# Anti_thept2ENGINE_-V2_2.net
KiCad netlist of a schematic drawn in EAGLE
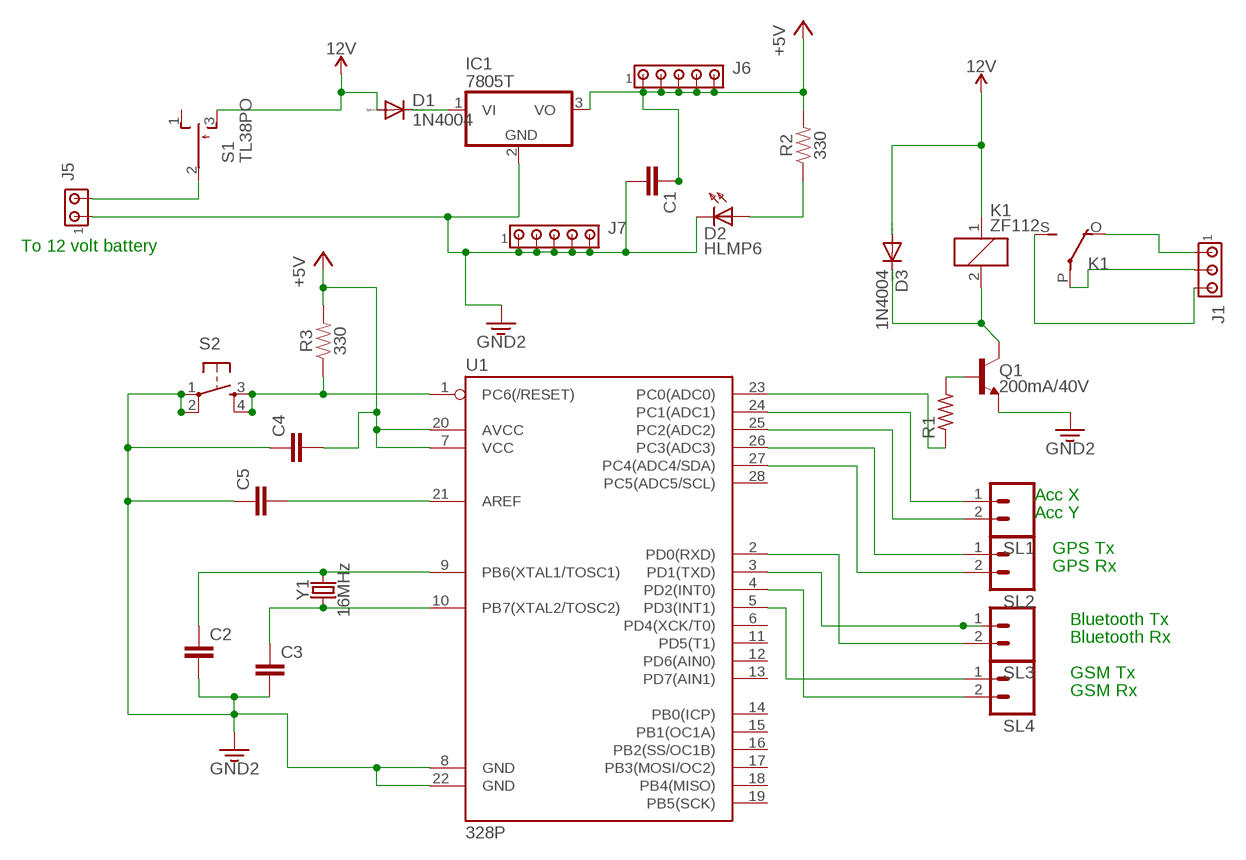
[diagram p0: schematic, sheet 1]

(export (version "E")
  (design (tool "Eeschema 10.0.6"))
  (components
    (comp (ref "C1")
      (value "C5/2.5")
      (footprint "eagle-import:C5B2.5")
      (libsource (lib "eagle-import") (part "C5/2.5"))
    )
    (comp (ref "C2")
      (value "C5/2.5")
      (footprint "eagle-import:C5B2.5")
      (libsource (lib "eagle-import") (part "C5/2.5"))
    )
    (comp (ref "C3")
      (value "C5/2.5")
      (footprint "eagle-import:C5B2.5")
      (libsource (lib "eagle-import") (part "C5/2.5"))
    )
    (comp (ref "C4")
      (value "C5/2.5")
      (footprint "eagle-import:C5B2.5")
      (libsource (lib "eagle-import") (part "C5/2.5"))
    )
    (comp (ref "C5")
      (value "C5/2.5")
      (footprint "eagle-import:C5B2.5")
      (libsource (lib "eagle-import") (part "C5/2.5"))
    )
    (comp (ref "D1")
      (value "1N4004")
      (footprint "eagle-import:DO41-10")
      (libsource (lib "eagle-import") (part "1N4004"))
    )
    (comp (ref "D2")
      (value "HLMP6")
      (footprint "eagle-import:HLMP6")
      (fields (field (name "MF") "AGILENT TECHNOLOGIES") (field (name "MPN") "HLMP-6500"))
      (libsource (lib "eagle-import") (part "HLMP6"))
    )
    (comp (ref "D3")
      (value "1N4004")
      (footprint "eagle-import:DO41-10")
      (libsource (lib "eagle-import") (part "1N4004"))
    )
    (comp (ref "IC1")
      (value "7805T")
      (footprint "eagle-import:TO220H")
      (libsource (lib "eagle-import") (part "78T05"))
    )
    (comp (ref "J1")
      (value "MTA03-156")
      (footprint "eagle-import:1X3MTA")
      (libsource (lib "eagle-import") (part "MTA03-156"))
    )
    (comp (ref "J5")
      (value "MTA02-156")
      (footprint "eagle-import:1X2MTA")
      (libsource (lib "eagle-import") (part "MTA02-156"))
    )
    (comp (ref "J6")
      (value "MTA05-100")
      (footprint "eagle-import:10X05MTA")
      (libsource (lib "eagle-import") (part "MTA05-100"))
    )
    (comp (ref "J7")
      (value "MTA05-100")
      (footprint "eagle-import:10X05MTA")
      (libsource (lib "eagle-import") (part "MTA05-100"))
    )
    (comp (ref "K1")
      (value "ZF112")
      (footprint "eagle-import:ZF112")
      (libsource (lib "eagle-import") (part "ZF112"))
    )
    (comp (ref "Q1")
      (value "200mA/40V")
      (footprint "eagle-import:TO-92")
      (libsource (lib "eagle-import") (part "TRANS_NPN-2N3904"))
    )
    (comp (ref "R1")
      (value "R-US_0204/7")
      (footprint "eagle-import:0204_7")
      (libsource (lib "eagle-import") (part "R-US_0204/7"))
    )
    (comp (ref "R2")
      (value "330")
      (footprint "eagle-import:AXIAL-0.3")
      (libsource (lib "eagle-import") (part "330OHM-HORIZ-1/10W-5%"))
    )
    (comp (ref "R3")
      (value "330")
      (footprint "eagle-import:AXIAL-0.3")
      (libsource (lib "eagle-import") (part "330OHM-HORIZ-1/10W-5%"))
    )
    (comp (ref "S1")
      (value "TL38PO")
      (footprint "eagle-import:TL3XPO")
      (libsource (lib "eagle-import") (part "TL38PO"))
    )
    (comp (ref "S2")
      (value "TAC_SWITCHPTH")
      (footprint "eagle-import:TACTILE-PTH")
      (libsource (lib "eagle-import") (part "TAC_SWITCHPTH"))
    )
    (comp (ref "SL1")
      (value "MA02")
      (footprint "eagle-import:02PA")
      (libsource (lib "eagle-import") (part "MA02"))
    )
    (comp (ref "SL2")
      (value "MA02")
      (footprint "eagle-import:02PA")
      (libsource (lib "eagle-import") (part "MA02"))
    )
    (comp (ref "SL3")
      (value "MA02")
      (footprint "eagle-import:02PA")
      (libsource (lib "eagle-import") (part "MA02"))
    )
    (comp (ref "SL4")
      (value "MA02")
      (footprint "eagle-import:02PA")
      (libsource (lib "eagle-import") (part "MA02"))
    )
    (comp (ref "U1")
      (value "328P")
      (footprint "eagle-import:DIP28")
      (libsource (lib "eagle-import") (part "ATMEGA328P_PDIP"))
    )
    (comp (ref "Y1")
      (value "16MHz")
      (footprint "eagle-import:HC49US")
      (libsource (lib "eagle-import") (part "CRYSTAL-16MHZPTH-HC49US"))
    )
  )
  (nets
    (net (code "1") (name "+5V") (class "Default")
      (node (ref "C1") (pin "1") (pinfunction "1_1") (pintype "passive"))
      (node (ref "C4") (pin "2") (pinfunction "2_2") (pintype "passive"))
      (node (ref "IC1") (pin "3") (pinfunction "VO_3") (pintype "passive"))
      (node (ref "J6") (pin "1") (pinfunction "1_1") (pintype "passive"))
      (node (ref "J6") (pin "2") (pinfunction "2_2") (pintype "passive"))
      (node (ref "J6") (pin "3") (pinfunction "3_3") (pintype "passive"))
      (node (ref "J6") (pin "4") (pinfunction "4_4") (pintype "passive"))
      (node (ref "J6") (pin "5") (pinfunction "5_5") (pintype "passive"))
      (node (ref "R2") (pin "P$2") (pinfunction "2_P$2") (pintype "passive"))
      (node (ref "R3") (pin "P$2") (pinfunction "2_P$2") (pintype "passive"))
      (node (ref "U1") (pin "20") (pinfunction "AVCC_20") (pintype "bidirectional"))
      (node (ref "U1") (pin "7") (pinfunction "VCC_7") (pintype "bidirectional"))
    )
    (net (code "2") (name "12V") (class "Default")
      (node (ref "D1") (pin "A") (pinfunction "A_A") (pintype "passive"))
      (node (ref "D3") (pin "A") (pinfunction "A_A") (pintype "passive"))
      (node (ref "K1") (pin "1") (pinfunction "1_1") (pintype "passive"))
      (node (ref "S1") (pin "3") (pinfunction "S_3") (pintype "passive"))
    )
    (net (code "3") (name "GND2") (class "Default")
      (node (ref "C1") (pin "2") (pinfunction "2_2") (pintype "passive"))
      (node (ref "C2") (pin "2") (pinfunction "2_2") (pintype "passive"))
      (node (ref "C3") (pin "2") (pinfunction "2_2") (pintype "passive"))
      (node (ref "C4") (pin "1") (pinfunction "1_1") (pintype "passive"))
      (node (ref "C5") (pin "1") (pinfunction "1_1") (pintype "passive"))
      (node (ref "D2") (pin "K") (pinfunction "K_K") (pintype "passive"))
      (node (ref "IC1") (pin "2") (pinfunction "GND_2") (pintype "passive"))
      (node (ref "J5") (pin "1") (pinfunction "1_1") (pintype "passive"))
      (node (ref "J7") (pin "1") (pinfunction "1_1") (pintype "passive"))
      (node (ref "J7") (pin "2") (pinfunction "2_2") (pintype "passive"))
      (node (ref "J7") (pin "3") (pinfunction "3_3") (pintype "passive"))
      (node (ref "J7") (pin "4") (pinfunction "4_4") (pintype "passive"))
      (node (ref "J7") (pin "5") (pinfunction "5_5") (pintype "passive"))
      (node (ref "Q1") (pin "1") (pinfunction "E_1") (pintype "passive"))
      (node (ref "S2") (pin "1") (pinfunction "1_1") (pintype "passive"))
      (node (ref "S2") (pin "2") (pinfunction "2_2") (pintype "passive"))
      (node (ref "U1") (pin "22") (pinfunction "GND_22") (pintype "bidirectional"))
      (node (ref "U1") (pin "8") (pinfunction "GND_8") (pintype "bidirectional"))
    )
    (net (code "4") (name "Net-(IC1-VI)") (class "Default")
      (node (ref "D1") (pin "C") (pinfunction "C_C") (pintype "passive"))
      (node (ref "IC1") (pin "1") (pinfunction "VI_1") (pintype "input"))
    )
    (net (code "5") (name "Net-(J1-Pad1)") (class "Default")
      (node (ref "J1") (pin "1") (pinfunction "1_1") (pintype "passive"))
      (node (ref "K1") (pin "O") (pinfunction "O_O") (pintype "passive"))
    )
    (net (code "6") (name "Net-(J1-Pad2)") (class "Default")
      (node (ref "J1") (pin "2") (pinfunction "2_2") (pintype "passive"))
      (node (ref "K1") (pin "P") (pinfunction "P_P") (pintype "passive"))
    )
    (net (code "7") (name "Net-(J1-Pad3)") (class "Default")
      (node (ref "J1") (pin "3") (pinfunction "3_3") (pintype "passive"))
      (node (ref "K1") (pin "S") (pinfunction "S_S") (pintype "passive"))
    )
    (net (code "8") (name "Net-(Q1-B)") (class "Default")
      (node (ref "Q1") (pin "2") (pinfunction "B_2") (pintype "passive"))
      (node (ref "R1") (pin "2") (pinfunction "2_2") (pintype "passive"))
    )
    (net (code "9") (name "Net-(Q1-C)") (class "Default")
      (node (ref "D3") (pin "C") (pinfunction "C_C") (pintype "passive"))
      (node (ref "K1") (pin "2") (pinfunction "2_2") (pintype "passive"))
      (node (ref "Q1") (pin "3") (pinfunction "C_3") (pintype "passive"))
    )
    (net (code "10") (name "Net-(R2-1)") (class "Default")
      (node (ref "D2") (pin "A") (pinfunction "A_A") (pintype "passive"))
      (node (ref "R2") (pin "P$1") (pinfunction "1_P$1") (pintype "passive"))
    )
    (net (code "11") (name "Net-(R3-1)") (class "Default")
      (node (ref "R3") (pin "P$1") (pinfunction "1_P$1") (pintype "passive"))
      (node (ref "S2") (pin "3") (pinfunction "3_3") (pintype "passive"))
      (node (ref "S2") (pin "4") (pinfunction "4_4") (pintype "passive"))
      (node (ref "U1") (pin "1") (pinfunction "PC6(/RESET)_1") (pintype "bidirectional"))
    )
    (net (code "12") (name "Net-(S1-P)") (class "Default")
      (node (ref "J5") (pin "2") (pinfunction "2_2") (pintype "passive"))
      (node (ref "S1") (pin "2") (pinfunction "P_2") (pintype "passive"))
    )
    (net (code "13") (name "Net-(U1-AREF)") (class "Default")
      (node (ref "C5") (pin "2") (pinfunction "2_2") (pintype "passive"))
      (node (ref "U1") (pin "21") (pinfunction "AREF_21") (pintype "bidirectional"))
    )
    (net (code "14") (name "Net-(U1-PB6(XTAL1{slash}TOSC1))") (class "Default")
      (node (ref "C2") (pin "1") (pinfunction "1_1") (pintype "passive"))
      (node (ref "U1") (pin "9") (pinfunction "PB6(XTAL1/TOSC1)_9") (pintype "bidirectional"))
      (node (ref "Y1") (pin "2") (pinfunction "2_2") (pintype "passive"))
    )
    (net (code "15") (name "Net-(U1-PB7(XTAL2{slash}TOSC2))") (class "Default")
      (node (ref "C3") (pin "1") (pinfunction "1_1") (pintype "passive"))
      (node (ref "U1") (pin "10") (pinfunction "PB7(XTAL2/TOSC2)_10") (pintype "bidirectional"))
      (node (ref "Y1") (pin "1") (pinfunction "1_1") (pintype "passive"))
    )
    (net (code "16") (name "Net-(U1-PC0(ADC0))") (class "Default")
      (node (ref "R1") (pin "1") (pinfunction "1_1") (pintype "passive"))
      (node (ref "U1") (pin "23") (pinfunction "PC0(ADC0)_23") (pintype "bidirectional"))
    )
    (net (code "17") (name "Net-(U1-PC1(ADC1))") (class "Default")
      (node (ref "SL1") (pin "1") (pinfunction "1_1") (pintype "passive"))
      (node (ref "U1") (pin "24") (pinfunction "PC1(ADC1)_24") (pintype "bidirectional"))
    )
    (net (code "18") (name "Net-(U1-PC2(ADC2))") (class "Default")
      (node (ref "SL1") (pin "2") (pinfunction "2_2") (pintype "passive"))
      (node (ref "U1") (pin "25") (pinfunction "PC2(ADC2)_25") (pintype "bidirectional"))
    )
    (net (code "19") (name "Net-(U1-PC3(ADC3))") (class "Default")
      (node (ref "SL2") (pin "1") (pinfunction "1_1") (pintype "passive"))
      (node (ref "U1") (pin "26") (pinfunction "PC3(ADC3)_26") (pintype "bidirectional"))
    )
    (net (code "20") (name "Net-(U1-PC4(ADC4{slash}SDA))") (class "Default")
      (node (ref "SL2") (pin "2") (pinfunction "2_2") (pintype "passive"))
      (node (ref "U1") (pin "27") (pinfunction "PC4(ADC4/SDA)_27") (pintype "bidirectional"))
    )
    (net (code "21") (name "Net-(U1-PD0(RXD))") (class "Default")
      (node (ref "SL3") (pin "2") (pinfunction "2_2") (pintype "passive"))
      (node (ref "U1") (pin "2") (pinfunction "PD0(RXD)_2") (pintype "bidirectional"))
    )
    (net (code "22") (name "Net-(U1-PD1(TXD))") (class "Default")
      (node (ref "SL3") (pin "1") (pinfunction "1_1") (pintype "passive"))
      (node (ref "U1") (pin "3") (pinfunction "PD1(TXD)_3") (pintype "bidirectional"))
    )
    (net (code "23") (name "Net-(U1-PD2(INT0))") (class "Default")
      (node (ref "SL4") (pin "2") (pinfunction "2_2") (pintype "passive"))
      (node (ref "U1") (pin "4") (pinfunction "PD2(INT0)_4") (pintype "bidirectional"))
    )
    (net (code "24") (name "Net-(U1-PD3(INT1))") (class "Default")
      (node (ref "SL4") (pin "1") (pinfunction "1_1") (pintype "passive"))
      (node (ref "U1") (pin "5") (pinfunction "PD3(INT1)_5") (pintype "bidirectional"))
    )
    (net (code "25") (name "unconnected-(S1-O-Pad1)") (class "Default")
      (node (ref "S1") (pin "1") (pinfunction "O_1") (pintype "passive"))
    )
    (net (code "26") (name "unconnected-(U1-PB0(ICP)-Pad14)") (class "Default")
      (node (ref "U1") (pin "14") (pinfunction "PB0(ICP)_14") (pintype "bidirectional"))
    )
    (net (code "27") (name "unconnected-(U1-PB1(OC1A)-Pad15)") (class "Default")
      (node (ref "U1") (pin "15") (pinfunction "PB1(OC1A)_15") (pintype "bidirectional"))
    )
    (net (code "28") (name "unconnected-(U1-PB2(SS{slash}OC1B)-Pad16)") (class "Default")
      (node (ref "U1") (pin "16") (pinfunction "PB2(SS/OC1B)_16") (pintype "bidirectional"))
    )
    (net (code "29") (name "unconnected-(U1-PB3(MOSI{slash}OC2)-Pad17)") (class "Default")
      (node (ref "U1") (pin "17") (pinfunction "PB3(MOSI/OC2)_17") (pintype "bidirectional"))
    )
    (net (code "30") (name "unconnected-(U1-PB4(MISO)-Pad18)") (class "Default")
      (node (ref "U1") (pin "18") (pinfunction "PB4(MISO)_18") (pintype "bidirectional"))
    )
    (net (code "31") (name "unconnected-(U1-PB5(SCK)-Pad19)") (class "Default")
      (node (ref "U1") (pin "19") (pinfunction "PB5(SCK)_19") (pintype "bidirectional"))
    )
    (net (code "32") (name "unconnected-(U1-PC5(ADC5{slash}SCL)-Pad28)") (class "Default")
      (node (ref "U1") (pin "28") (pinfunction "PC5(ADC5/SCL)_28") (pintype "bidirectional"))
    )
    (net (code "33") (name "unconnected-(U1-PD4(XCK{slash}T0)-Pad6)") (class "Default")
      (node (ref "U1") (pin "6") (pinfunction "PD4(XCK/T0)_6") (pintype "bidirectional"))
    )
    (net (code "34") (name "unconnected-(U1-PD5(T1)-Pad11)") (class "Default")
      (node (ref "U1") (pin "11") (pinfunction "PD5(T1)_11") (pintype "bidirectional"))
    )
    (net (code "35") (name "unconnected-(U1-PD6(AIN0)-Pad12)") (class "Default")
      (node (ref "U1") (pin "12") (pinfunction "PD6(AIN0)_12") (pintype "bidirectional"))
    )
    (net (code "36") (name "unconnected-(U1-PD7(AIN1)-Pad13)") (class "Default")
      (node (ref "U1") (pin "13") (pinfunction "PD7(AIN1)_13") (pintype "bidirectional"))
    )
  )
)
